# ADC.net
KiCad netlist of a schematic drawn in Altium Designer
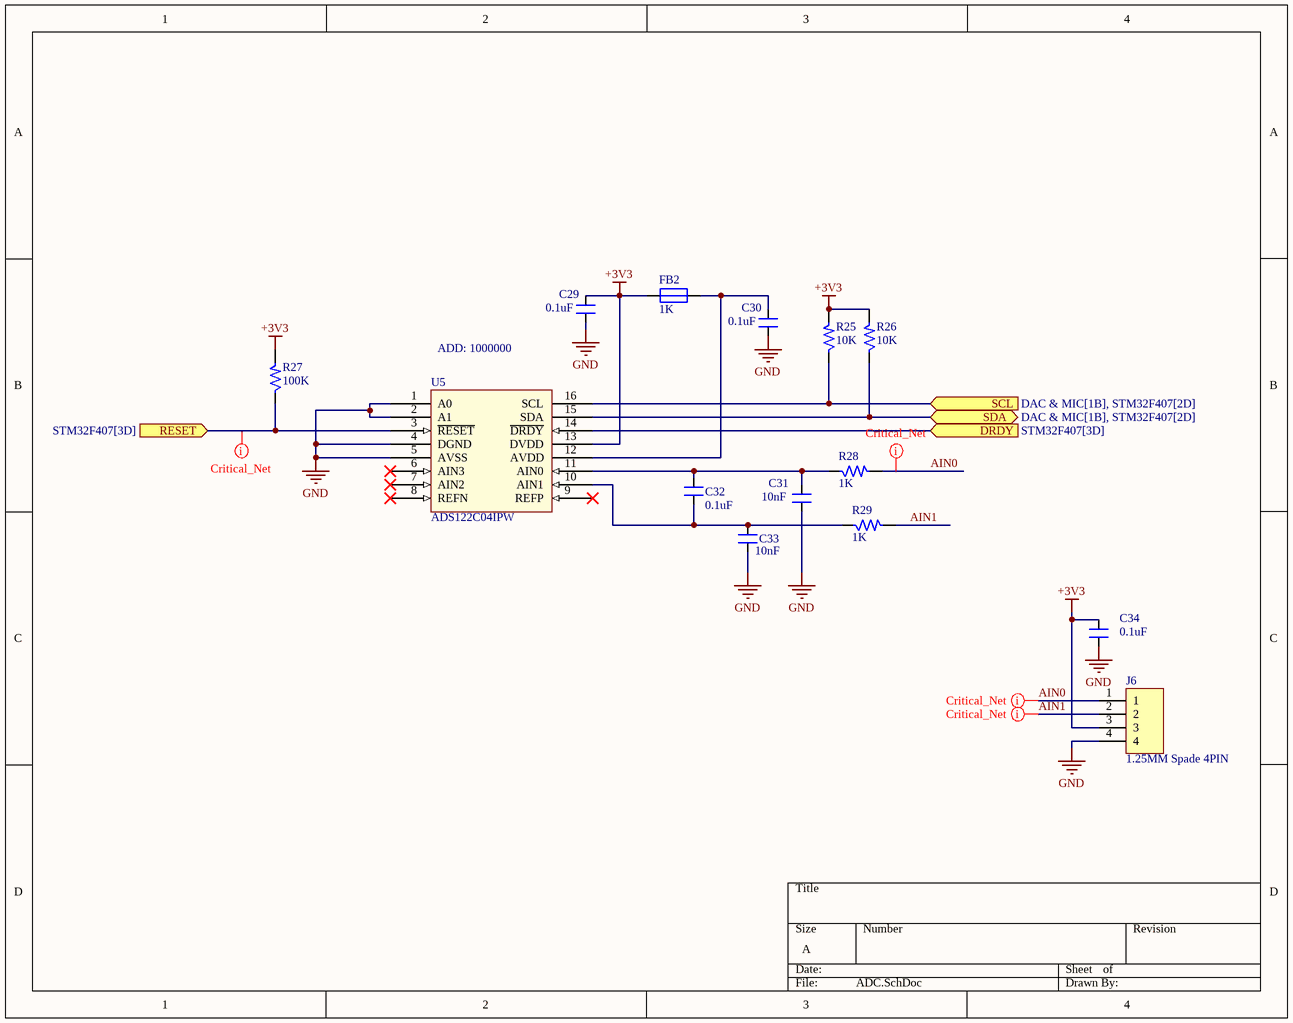
[diagram p0: ADC.SchDoc]

(export (version "E")
  (design (tool "Eeschema 10.0.6"))
  (components
    (comp (ref "C29")
      (value "0.1uF")
      (footprint "CAP_0805")
      (description "0.1µF ±10% 50V Ceramic Capacitor X7R 0805 (2012 Metric)")
      (fields
        (field (name "MANUFACTURER") "Samsung")
        (field (name "MANUFACTURER PART NUMBER") "CL21B104KBCNNNC")
      )
      (libsource (lib "ESTEEMPCBLIB") (part "CAP_0.1uF-50V-10%-0805"))
    )
    (comp (ref "C30")
      (value "0.1uF")
      (footprint "CAP_0805")
      (description "0.1µF ±10% 50V Ceramic Capacitor X7R 0805 (2012 Metric)")
      (fields
        (field (name "MANUFACTURER") "Samsung")
        (field (name "MANUFACTURER PART NUMBER") "CL21B104KBCNNNC")
      )
      (libsource (lib "ESTEEMPCBLIB") (part "CAP_0.1uF-50V-10%-0805"))
    )
    (comp (ref "C31")
      (value "10nF")
      (footprint "CAP_0805")
      (description "10000pF ±10% 50V Ceramic Capacitor X7R 0805 (2012 Metric)")
      (fields
        (field (name "MANUFACTURER") "Samsung")
        (field (name "MANUFACTURER PART NUMBER") "C0805C103K5RECAUTO")
      )
      (libsource (lib "ESTEEMPCBLIB") (part "CAP_10nF-50V-10%-0805"))
    )
    (comp (ref "C32")
      (value "0.1uF")
      (footprint "CAP_0805")
      (description "0.1µF ±10% 50V Ceramic Capacitor X7R 0805 (2012 Metric)")
      (fields
        (field (name "MANUFACTURER") "Samsung")
        (field (name "MANUFACTURER PART NUMBER") "CL21B104KBCNNNC")
      )
      (libsource (lib "ESTEEMPCBLIB") (part "CAP_0.1uF-50V-10%-0805"))
    )
    (comp (ref "C33")
      (value "10nF")
      (footprint "CAP_0805")
      (description "10000pF ±10% 50V Ceramic Capacitor X7R 0805 (2012 Metric)")
      (fields
        (field (name "MANUFACTURER") "Samsung")
        (field (name "MANUFACTURER PART NUMBER") "C0805C103K5RECAUTO")
      )
      (libsource (lib "ESTEEMPCBLIB") (part "CAP_10nF-50V-10%-0805"))
    )
    (comp (ref "C34")
      (value "0.1uF")
      (footprint "CAP_0805")
      (description "0.1µF ±10% 50V Ceramic Capacitor X7R 0805 (2012 Metric)")
      (fields
        (field (name "MANUFACTURER") "Samsung")
        (field (name "MANUFACTURER PART NUMBER") "CL21B104KBCNNNC")
      )
      (libsource (lib "ESTEEMPCBLIB") (part "CAP_0.1uF-50V-10%-0805"))
    )
    (comp (ref "FB2")
      (value "1K")
      (footprint "IND_0805")
      (description "1 kOhms @ 100MHz 1 Power Line Ferrite Bead 0805 (2012 Metric) 1.6A")
      (fields
        (field (name "MANUFACTURER") "Laird")
        (field (name "MANUFACTURER PART NUMBER") "BLM21SP102SH1D")
      )
      (libsource (lib "ESTEEMPCBLIB") (part "FB_1K-100MHZ-1.6A-0805"))
    )
    (comp (ref "J6")
      (value "1.25MM Spade 4PIN")
      (footprint "CON4_50_653004117322_TH_RA")
      (description "4 Pins, 1 Row 1.25mm Pitch, right angle Connector, male")
      (fields (field (name "MANUFACTURER PART NUMBER") "653004117322") (field (name "MANUFACTURER") "JST"))
      (libsource (lib "ESTEEMPCBLIB") (part "CON-PLG_4X1-50-RA-TH"))
    )
    (comp (ref "R25")
      (value "10K")
      (footprint "RES_0603")
      (description "10 kOhms ±1% 0.1W, 1/10W Chip Resistor 0603 (1608 Metric) Automotive AEC-Q200 Thick Film")
      (fields (field (name "MANUFACTURER") "Walsin") (field (name "MANUFACTURER PART NUMBER") "WR06X1002FTL"))
      (libsource (lib "ESTEEMPCBLIB") (part "RES_10K-0.1W-1%-0603"))
    )
    (comp (ref "R26")
      (value "10K")
      (footprint "RES_0603")
      (description "10 kOhms ±1% 0.1W, 1/10W Chip Resistor 0603 (1608 Metric) Automotive AEC-Q200 Thick Film")
      (fields (field (name "MANUFACTURER") "Walsin") (field (name "MANUFACTURER PART NUMBER") "WR06X1002FTL"))
      (libsource (lib "ESTEEMPCBLIB") (part "RES_10K-0.1W-1%-0603"))
    )
    (comp (ref "R27")
      (value "100K")
      (footprint "RES_0603")
      (description "100 kOhms ±1% 0.1W, 1/10W Chip Resistor 0603 (1608 Metric) Automotive AEC-Q200 Thick Film")
      (fields
        (field (name "MANUFACTURER") "Stackpole Electronics")
        (field (name "MANUFACTURER PART NUMBER") "RMCF0603FT100K")
      )
      (libsource (lib "ESTEEMPCBLIB") (part "RES_100K-0.1W-1%-0603"))
    )
    (comp (ref "R28")
      (value "1K")
      (footprint "RES_0603")
      (description "1 kOhms ±1% 0.1W, 1/10W Chip Resistor 0603 (1608 Metric) Automotive AEC-Q200 Thick Film")
      (fields (field (name "MANUFACTURER") "Walsin") (field (name "MANUFACTURER PART NUMBER") "WR06X1001FTL"))
      (libsource (lib "ESTEEMPCBLIB") (part "RES_1K-0.1W-1%-0603"))
    )
    (comp (ref "R29")
      (value "1K")
      (footprint "RES_0603")
      (description "1 kOhms ±1% 0.1W, 1/10W Chip Resistor 0603 (1608 Metric) Automotive AEC-Q200 Thick Film")
      (fields (field (name "MANUFACTURER") "Walsin") (field (name "MANUFACTURER PART NUMBER") "WR06X1001FTL"))
      (libsource (lib "ESTEEMPCBLIB") (part "RES_1K-0.1W-1%-0603"))
    )
    (comp (ref "U5")
      (value "ADS122C04IPW")
      (footprint "TSSOP16_25-59_294_54X14_SMT")
      (description "24 Bit Analog to Digital Converter 4 Input 1 Sigma-Delta 16-TSSOP")
      (fields (field (name "MANUFACTURER") "Texas Instruments"))
      (libsource (lib "ESTEEMPCBLIB") (part "IC_ADS122C04IPW"))
    )
  )
  (nets
    (net (code "1") (name "+3V3") (class "Default")
      (node (ref "C29") (pin "2") (pinfunction "2_2") (pintype "passive"))
      (node (ref "C34") (pin "2") (pinfunction "2_2") (pintype "passive"))
      (node (ref "FB2") (pin "1") (pinfunction "1_1") (pintype "passive"))
      (node (ref "J6") (pin "3") (pinfunction "3_3") (pintype "passive"))
      (node (ref "R25") (pin "2") (pinfunction "2_2") (pintype "passive"))
      (node (ref "R26") (pin "2") (pinfunction "2_2") (pintype "passive"))
      (node (ref "R27") (pin "2") (pinfunction "2_2") (pintype "passive"))
      (node (ref "U5") (pin "13") (pinfunction "DVDD_13") (pintype "power_in"))
    )
    (net (code "2") (name "/AIN0") (class "Default")
      (node (ref "J6") (pin "1") (pinfunction "1_1") (pintype "passive"))
      (node (ref "R28") (pin "2") (pinfunction "2_2") (pintype "passive"))
    )
    (net (code "3") (name "/AIN1") (class "Default")
      (node (ref "J6") (pin "2") (pinfunction "2_2") (pintype "passive"))
      (node (ref "R29") (pin "2") (pinfunction "2_2") (pintype "passive"))
    )
    (net (code "4") (name "/DRDY") (class "Default")
      (node (ref "U5") (pin "14") (pinfunction "DRDY_14") (pintype "input"))
    )
    (net (code "5") (name "/RESET") (class "Default")
      (node (ref "R27") (pin "1") (pinfunction "1_1") (pintype "passive"))
      (node (ref "U5") (pin "3") (pinfunction "RESET_3") (pintype "input"))
    )
    (net (code "6") (name "/SCL") (class "Default")
      (node (ref "R25") (pin "1") (pinfunction "1_1") (pintype "passive"))
      (node (ref "U5") (pin "16") (pinfunction "SCL_16") (pintype "open_collector"))
    )
    (net (code "7") (name "/SDA") (class "Default")
      (node (ref "R26") (pin "1") (pinfunction "1_1") (pintype "passive"))
      (node (ref "U5") (pin "15") (pinfunction "SDA_15") (pintype "open_collector"))
    )
    (net (code "8") (name "GND") (class "Default")
      (node (ref "C29") (pin "1") (pinfunction "1_1") (pintype "passive"))
      (node (ref "C30") (pin "1") (pinfunction "1_1") (pintype "passive"))
      (node (ref "C31") (pin "1") (pinfunction "1_1") (pintype "passive"))
      (node (ref "C33") (pin "1") (pinfunction "1_1") (pintype "passive"))
      (node (ref "C34") (pin "1") (pinfunction "1_1") (pintype "passive"))
      (node (ref "J6") (pin "4") (pinfunction "4_4") (pintype "passive"))
      (node (ref "U5") (pin "1") (pinfunction "A0_1") (pintype "passive"))
      (node (ref "U5") (pin "2") (pinfunction "A1_2") (pintype "passive"))
      (node (ref "U5") (pin "4") (pinfunction "DGND_4") (pintype "power_in"))
      (node (ref "U5") (pin "5") (pinfunction "AVSS_5") (pintype "power_in"))
    )
    (net (code "9") (name "Net-(U5-AIN0)") (class "Default")
      (node (ref "C31") (pin "2") (pinfunction "2_2") (pintype "passive"))
      (node (ref "C32") (pin "2") (pinfunction "2_2") (pintype "passive"))
      (node (ref "R28") (pin "1") (pinfunction "1_1") (pintype "passive"))
      (node (ref "U5") (pin "11") (pinfunction "AIN0_11") (pintype "input"))
    )
    (net (code "10") (name "Net-(U5-AIN1)") (class "Default")
      (node (ref "C32") (pin "1") (pinfunction "1_1") (pintype "passive"))
      (node (ref "C33") (pin "2") (pinfunction "2_2") (pintype "passive"))
      (node (ref "R29") (pin "1") (pinfunction "1_1") (pintype "passive"))
      (node (ref "U5") (pin "10") (pinfunction "AIN1_10") (pintype "input"))
    )
    (net (code "11") (name "Net-(U5-AVDD)") (class "Default")
      (node (ref "C30") (pin "2") (pinfunction "2_2") (pintype "passive"))
      (node (ref "FB2") (pin "2") (pinfunction "2_2") (pintype "passive"))
      (node (ref "U5") (pin "12") (pinfunction "AVDD_12") (pintype "power_in"))
    )
    (net (code "12") (name "unconnected-(U5-AIN2-Pad7)") (class "Default")
      (node (ref "U5") (pin "7") (pinfunction "AIN2_7") (pintype "input+no_connect"))
    )
    (net (code "13") (name "unconnected-(U5-AIN3-Pad6)") (class "Default")
      (node (ref "U5") (pin "6") (pinfunction "AIN3_6") (pintype "input+no_connect"))
    )
    (net (code "14") (name "unconnected-(U5-REFN-Pad8)") (class "Default")
      (node (ref "U5") (pin "8") (pinfunction "REFN_8") (pintype "input+no_connect"))
    )
    (net (code "15") (name "unconnected-(U5-REFP-Pad9)") (class "Default")
      (node (ref "U5") (pin "9") (pinfunction "REFP_9") (pintype "input+no_connect"))
    )
  )
)
